# TopSheet.net
KiCad netlist of a schematic drawn in Altium Designer
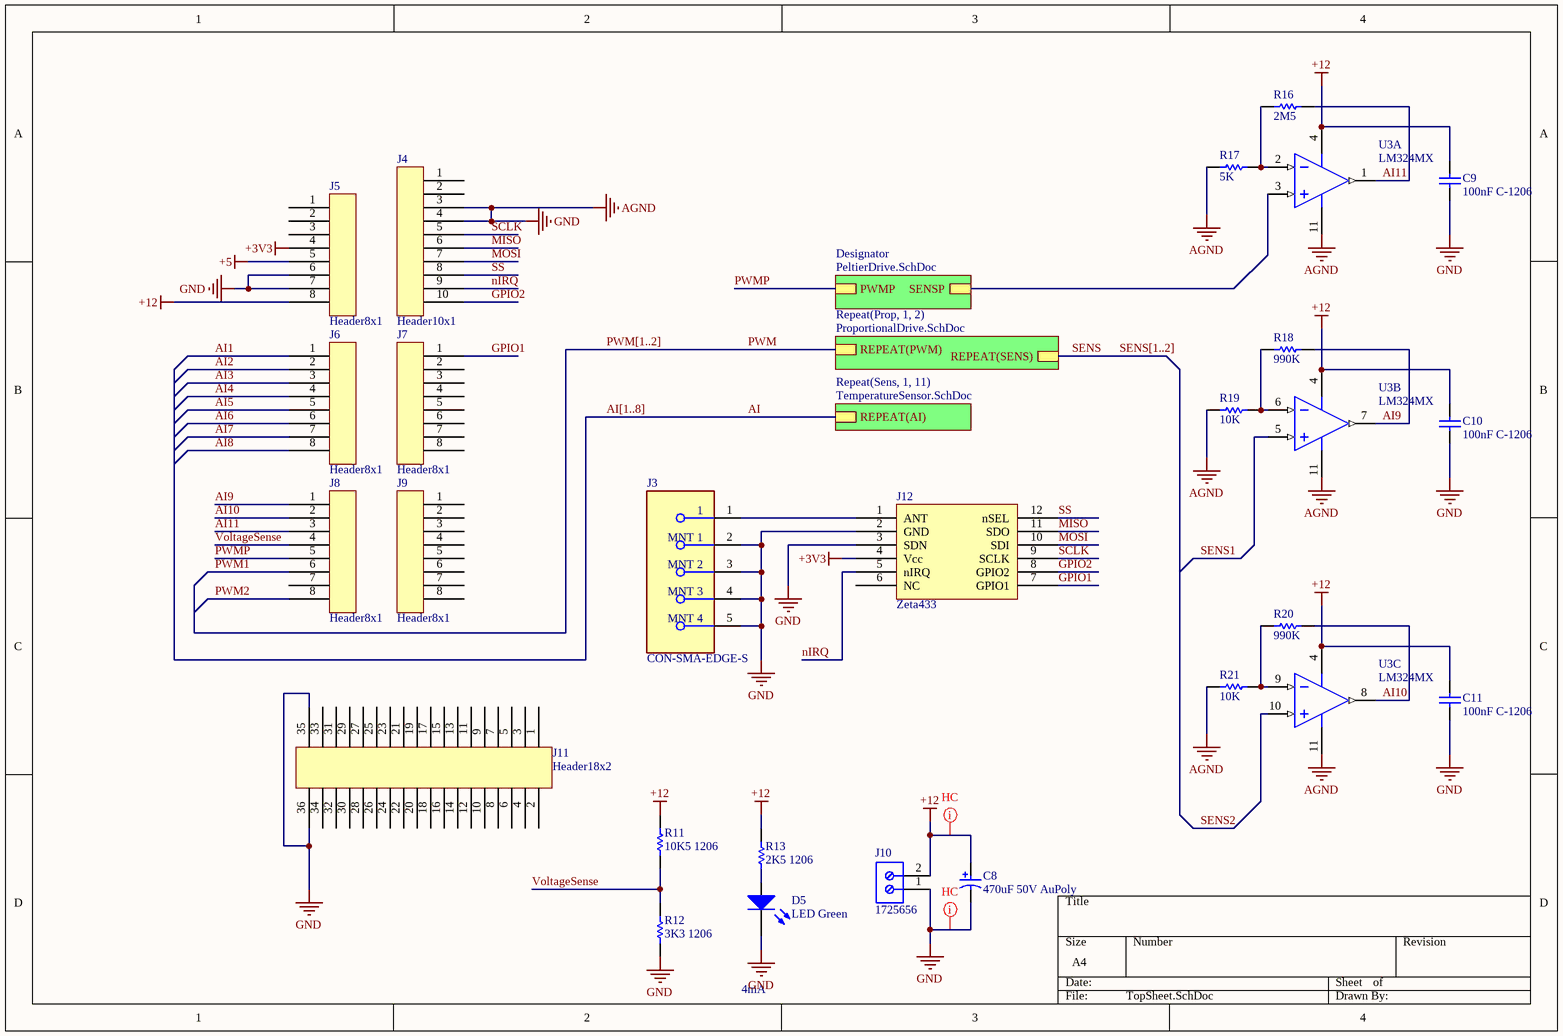
[diagram p0: TopSheet.SchDoc]

(export (version "E")
  (design (tool "Eeschema 10.0.6"))
  (components
    (comp (ref "C8")
      (value "470uF 50V AuPoly")
      (footprint "CAPAE137130X163M")
      (fields (field (name "VOLTAGE") "25VDC") (field (name "MANUFACTURER") "AVX"))
      (libsource (lib "Schlib1") (part "C-Poly"))
    )
    (comp (ref "C9")
      (value "100nF C-1206")
      (footprint "C-1206")
      (description "Ceramic 50V 1206")
      (fields (field (name "TOLERANCE") "Â±20%"))
      (libsource (lib "Schlib1") (part "C-1206"))
    )
    (comp (ref "C10")
      (value "100nF C-1206")
      (footprint "C-1206")
      (description "Ceramic 50V 1206")
      (fields (field (name "TOLERANCE") "Â±20%"))
      (libsource (lib "Schlib1") (part "C-1206"))
    )
    (comp (ref "C11")
      (value "100nF C-1206")
      (footprint "C-1206")
      (description "Ceramic 50V 1206")
      (fields (field (name "TOLERANCE") "Â±20%"))
      (libsource (lib "Schlib1") (part "C-1206"))
    )
    (comp (ref "D5")
      (value "LED Green")
      (footprint "0603_A")
      (description "SMD mono-color Chip LED, WL-SMCW, Green")
      (fields (field (name "PARTNUMBER") "150060GS75000") (field (name "MANUFACTURER") "Wuerth Elektronik"))
      (libsource (lib "Altium Content Vault") (part "WE-LED_K1A2-2"))
    )
    (comp (ref "J3")
      (value "CON-SMA-EDGE-S")
      (footprint "FP-CON-SMA-EDGE-S-MFG")
      (description "CONN SMA JACK STR EDGE MNT")
      (fields
        (field (name "OCTOPART") "https://octopart.com/con-sma-edge-s-rf+solutions-70967450")
        (field (name "MANUFACTURER") "RF Solutions Ltd.")
      )
      (libsource (lib "Altium Content Vault") (part "a163d97a771fcdd2fd1f1a9264c171f"))
    )
    (comp (ref "J4")
      (value "Header10x1")
      (footprint "Header10x1")
      (libsource (lib "Schlib1") (part "Header10x1"))
    )
    (comp (ref "J5")
      (value "Header8x1")
      (footprint "Header8x1")
      (libsource (lib "Schlib1") (part "Header8x1"))
    )
    (comp (ref "J6")
      (value "Header8x1")
      (footprint "Header8x1")
      (libsource (lib "Schlib1") (part "Header8x1"))
    )
    (comp (ref "J7") (value "Header8x1") (footprint "Header8x1") (libsource (lib "") (part "Header8x1_1")))
    (comp (ref "J8")
      (value "Header8x1")
      (footprint "Header8x1")
      (libsource (lib "Schlib1") (part "Header8x1"))
    )
    (comp (ref "J9") (value "Header8x1") (footprint "Header8x1") (libsource (lib "") (part "Header8x1_1")))
    (comp (ref "J10")
      (value "1725656")
      (footprint "PHOE-1725656-2")
      (description "Male Header, Pitch 2.54 mm, 1 x 2 Position, Height 9 mm, Tail Length 3.5 mm")
      (fields (field (name "MANUFACTURER") "Phoenix Contact"))
      (libsource (lib "Altium Content Vault") (part "CN-1P-F-TB2"))
    )
    (comp (ref "J11")
      (value "Header18x2")
      (footprint "Header18x2")
      (libsource (lib "Schlib1") (part "Header18x2"))
    )
    (comp (ref "J12") (value "Zeta433") (footprint "Zeta433-SM") (libsource (lib "Schlib1") (part "Zeta433")))
    (comp (ref "R11")
      (value "10K5 1206")
      (footprint "R-1206")
      (description "0.25W 1206")
      (fields (field (name "POWER") "0.1 W") (field (name "TOLERANCE") "1 %"))
      (libsource (lib "Schlib1") (part "R-1206"))
    )
    (comp (ref "R12")
      (value "3K3 1206")
      (footprint "R-1206")
      (description "0.25W 1206")
      (fields (field (name "POWER") "0.1 W") (field (name "TOLERANCE") "1 %"))
      (libsource (lib "Schlib1") (part "R-1206"))
    )
    (comp (ref "R13")
      (value "2K5 1206")
      (footprint "R-1206")
      (description "0.25W 1206")
      (fields (field (name "POWER") "0.1 W") (field (name "TOLERANCE") "1 %"))
      (libsource (lib "Schlib1") (part "R-1206"))
    )
    (comp (ref "R16")
      (value "2M5")
      (footprint "RESC0603(1608)_N")
      (description "10K 0.1W 1% 0603 (1608 Metric)  SMD")
      (fields (field (name "POWER") "0.1 W") (field (name "TOLERANCE") "1 %"))
      (libsource (lib "Altium Content Vault") (part "RES"))
    )
    (comp (ref "R17")
      (value "5K")
      (footprint "RESC0603(1608)_N")
      (description "10K 0.1W 1% 0603 (1608 Metric)  SMD")
      (fields (field (name "POWER") "0.1 W") (field (name "TOLERANCE") "1 %"))
      (libsource (lib "Altium Content Vault") (part "RES"))
    )
    (comp (ref "R18")
      (value "990K")
      (footprint "RESC0603(1608)_N")
      (description "10K 0.1W 1% 0603 (1608 Metric)  SMD")
      (fields (field (name "POWER") "0.1 W") (field (name "TOLERANCE") "1 %"))
      (libsource (lib "Altium Content Vault") (part "RES"))
    )
    (comp (ref "R19")
      (value "10K")
      (footprint "RESC0603(1608)_N")
      (description "10K 0.1W 1% 0603 (1608 Metric)  SMD")
      (fields (field (name "POWER") "0.1 W") (field (name "TOLERANCE") "1 %"))
      (libsource (lib "Altium Content Vault") (part "RES"))
    )
    (comp (ref "R20")
      (value "990K")
      (footprint "RESC0603(1608)_N")
      (description "10K 0.1W 1% 0603 (1608 Metric)  SMD")
      (fields (field (name "POWER") "0.1 W") (field (name "TOLERANCE") "1 %"))
      (libsource (lib "Altium Content Vault") (part "RES"))
    )
    (comp (ref "R21")
      (value "10K")
      (footprint "RESC0603(1608)_N")
      (description "10K 0.1W 1% 0603 (1608 Metric)  SMD")
      (fields (field (name "POWER") "0.1 W") (field (name "TOLERANCE") "1 %"))
      (libsource (lib "Altium Content Vault") (part "RES"))
    )
    (comp (ref "U3")
      (value "LM324MX")
      (footprint "D0014A_L")
      (description "Low Power Quad Operational Amplifier, 14-pin Narrow SOIC")
      (fields (field (name "MANUFACTURER") "Texas Instruments"))
      (libsource (lib "Altium Content Vault") (part "AMP-OPA-LM124-14"))
    )
  )
  (nets
    (net (code "1") (name "+3V3") (class "Default")
      (node (ref "J12") (pin "4") (pinfunction "Vcc_4") (pintype "passive"))
      (node (ref "J5") (pin "4") (pintype "passive"))
    )
    (net (code "2") (name "+5") (class "Default") (node (ref "J5") (pin "5") (pintype "passive")))
    (net (code "3") (name "+12") (class "Default")
      (node (ref "C10") (pin "2") (pinfunction "2_2") (pintype "passive"))
      (node (ref "C11") (pin "2") (pinfunction "2_2") (pintype "passive"))
      (node (ref "C8") (pin "1") (pinfunction "1_1") (pintype "passive"))
      (node (ref "C9") (pin "2") (pinfunction "2_2") (pintype "passive"))
      (node (ref "J10") (pin "2") (pinfunction "2_2") (pintype "passive"))
      (node (ref "J5") (pin "8") (pintype "passive"))
      (node (ref "R11") (pin "2") (pinfunction "2_2") (pintype "passive"))
      (node (ref "R13") (pin "2") (pinfunction "2_2") (pintype "passive"))
      (node (ref "U3") (pin "4") (pinfunction "V+_4") (pintype "power_in"))
    )
    (net (code "5") (name "/AI1") (class "Default") (node (ref "J6") (pin "1") (pintype "passive")))
    (net (code "6") (name "/AI2") (class "Default") (node (ref "J6") (pin "2") (pintype "passive")))
    (net (code "7") (name "/AI3") (class "Default") (node (ref "J6") (pin "3") (pintype "passive")))
    (net (code "8") (name "/AI4") (class "Default") (node (ref "J6") (pin "4") (pintype "passive")))
    (net (code "9") (name "/AI5") (class "Default") (node (ref "J6") (pin "5") (pintype "passive")))
    (net (code "10") (name "/AI6") (class "Default") (node (ref "J6") (pin "6") (pintype "passive")))
    (net (code "11") (name "/AI7") (class "Default") (node (ref "J6") (pin "7") (pintype "passive")))
    (net (code "12") (name "/AI8") (class "Default") (node (ref "J6") (pin "8") (pintype "passive")))
    (net (code "13") (name "/AI9") (class "Default")
      (node (ref "J8") (pin "1") (pintype "passive"))
      (node (ref "R18") (pin "2") (pinfunction "2_2") (pintype "passive"))
      (node (ref "U3") (pin "7") (pinfunction "OUT2_7") (pintype "output"))
    )
    (net (code "14") (name "/AI10") (class "Default")
      (node (ref "J8") (pin "2") (pintype "passive"))
      (node (ref "R20") (pin "2") (pinfunction "2_2") (pintype "passive"))
      (node (ref "U3") (pin "8") (pinfunction "OUT3_8") (pintype "output"))
    )
    (net (code "15") (name "/AI11") (class "Default")
      (node (ref "J8") (pin "3") (pintype "passive"))
      (node (ref "R16") (pin "2") (pinfunction "2_2") (pintype "passive"))
      (node (ref "U3") (pin "1") (pinfunction "OUT1_1") (pintype "output"))
    )
    (net (code "17") (name "/GPIO1") (class "Default")
      (node (ref "J12") (pin "7") (pinfunction "GPIO1_7") (pintype "passive"))
      (node (ref "J7") (pin "1") (pintype "passive"))
    )
    (net (code "18") (name "/GPIO2") (class "Default")
      (node (ref "J12") (pin "8") (pinfunction "GPIO2_8") (pintype "passive"))
      (node (ref "J4") (pin "10") (pintype "passive"))
    )
    (net (code "19") (name "/MISO") (class "Default")
      (node (ref "J12") (pin "11") (pinfunction "SDO_11") (pintype "passive"))
      (node (ref "J4") (pin "6") (pintype "passive"))
    )
    (net (code "20") (name "/MOSI") (class "Default")
      (node (ref "J12") (pin "10") (pinfunction "SDI_10") (pintype "passive"))
      (node (ref "J4") (pin "7") (pintype "passive"))
    )
    (net (code "22") (name "/PWM1") (class "Default") (node (ref "J8") (pin "6") (pintype "passive")))
    (net (code "23") (name "/PWM2") (class "Default") (node (ref "J8") (pin "8") (pintype "passive")))
    (net (code "24") (name "/PWMP") (class "Default") (node (ref "J8") (pin "5") (pintype "passive")))
    (net (code "26") (name "/SCLK") (class "Default")
      (node (ref "J12") (pin "9") (pinfunction "SCLK_9") (pintype "passive"))
      (node (ref "J4") (pin "5") (pintype "passive"))
    )
    (net (code "28") (name "/SENS1") (class "Default")
      (node (ref "U3") (pin "5") (pinfunction "IN2+_5") (pintype "input"))
    )
    (net (code "29") (name "/SENS2") (class "Default")
      (node (ref "U3") (pin "10") (pinfunction "IN3+_10") (pintype "input"))
    )
    (net (code "30") (name "/SENSP") (class "Default")
      (node (ref "U3") (pin "3") (pinfunction "IN1+_3") (pintype "input"))
    )
    (net (code "32") (name "/SS") (class "Default")
      (node (ref "J12") (pin "12") (pinfunction "nSEL_12") (pintype "passive"))
      (node (ref "J4") (pin "8") (pintype "passive"))
    )
    (net (code "33") (name "/VoltageSense") (class "Default")
      (node (ref "J8") (pin "4") (pintype "passive"))
      (node (ref "R11") (pin "1") (pinfunction "1_1") (pintype "passive"))
      (node (ref "R12") (pin "2") (pinfunction "2_2") (pintype "passive"))
    )
    (net (code "34") (name "/nIRQ") (class "Default")
      (node (ref "J12") (pin "5") (pinfunction "nIRQ_5") (pintype "passive"))
      (node (ref "J4") (pin "9") (pintype "passive"))
    )
    (net (code "35") (name "AGND") (class "Default")
      (node (ref "C10") (pin "1") (pinfunction "1_1") (pintype "passive"))
      (node (ref "C11") (pin "1") (pinfunction "1_1") (pintype "passive"))
      (node (ref "C8") (pin "2") (pinfunction "2_2") (pintype "passive"))
      (node (ref "C9") (pin "1") (pinfunction "1_1") (pintype "passive"))
      (node (ref "D5") (pin "1") (pinfunction "K_1") (pintype "passive"))
      (node (ref "J10") (pin "1") (pinfunction "1_1") (pintype "passive"))
      (node (ref "J11") (pin "35") (pintype "passive"))
      (node (ref "J11") (pin "36") (pintype "passive"))
      (node (ref "J12") (pin "2") (pinfunction "GND_2") (pintype "passive"))
      (node (ref "J12") (pin "3") (pinfunction "SDN_3") (pintype "passive"))
      (node (ref "J3") (pin "2") (pinfunction "MNT_1_2") (pintype "passive"))
      (node (ref "J3") (pin "3") (pinfunction "MNT_2_3") (pintype "passive"))
      (node (ref "J3") (pin "4") (pinfunction "MNT_3_4") (pintype "passive"))
      (node (ref "J3") (pin "5") (pinfunction "MNT_4_5") (pintype "passive"))
      (node (ref "J4") (pin "3") (pintype "passive"))
      (node (ref "J4") (pin "4") (pintype "passive"))
      (node (ref "J5") (pin "6") (pintype "passive"))
      (node (ref "J5") (pin "7") (pintype "passive"))
      (node (ref "R12") (pin "1") (pinfunction "1_1") (pintype "passive"))
      (node (ref "R17") (pin "1") (pinfunction "1_1") (pintype "passive"))
      (node (ref "R19") (pin "1") (pinfunction "1_1") (pintype "passive"))
      (node (ref "R21") (pin "1") (pinfunction "1_1") (pintype "passive"))
      (node (ref "U3") (pin "11") (pinfunction "GND_11") (pintype "power_in"))
    )
    (net (code "36") (name "Net-(D5-A)") (class "Default")
      (node (ref "D5") (pin "2") (pinfunction "A_2") (pintype "passive"))
      (node (ref "R13") (pin "1") (pinfunction "1_1") (pintype "passive"))
    )
    (net (code "37") (name "Net-(J12-ANT)") (class "Default")
      (node (ref "J12") (pin "1") (pinfunction "ANT_1") (pintype "passive"))
      (node (ref "J3") (pin "1") (pinfunction "1_1") (pintype "passive"))
    )
    (net (code "38") (name "Net-(U3A-IN1-)") (class "Default")
      (node (ref "R16") (pin "1") (pinfunction "1_1") (pintype "passive"))
      (node (ref "R17") (pin "2") (pinfunction "2_2") (pintype "passive"))
      (node (ref "U3") (pin "2") (pinfunction "IN1-_2") (pintype "input"))
    )
    (net (code "39") (name "Net-(U3B-IN2-)") (class "Default")
      (node (ref "R18") (pin "1") (pinfunction "1_1") (pintype "passive"))
      (node (ref "R19") (pin "2") (pinfunction "2_2") (pintype "passive"))
      (node (ref "U3") (pin "6") (pinfunction "IN2-_6") (pintype "input"))
    )
    (net (code "40") (name "Net-(U3C-IN3-)") (class "Default")
      (node (ref "R20") (pin "1") (pinfunction "1_1") (pintype "passive"))
      (node (ref "R21") (pin "2") (pinfunction "2_2") (pintype "passive"))
      (node (ref "U3") (pin "9") (pinfunction "IN3-_9") (pintype "input"))
    )
    (net (code "41") (name "unconnected-(J4-Pad1)") (class "Default")
      (node (ref "J4") (pin "1") (pintype "passive"))
    )
    (net (code "42") (name "unconnected-(J4-Pad2)") (class "Default")
      (node (ref "J4") (pin "2") (pintype "passive"))
    )
    (net (code "43") (name "unconnected-(J5-Pad1)") (class "Default")
      (node (ref "J5") (pin "1") (pintype "passive"))
    )
    (net (code "44") (name "unconnected-(J5-Pad2)") (class "Default")
      (node (ref "J5") (pin "2") (pintype "passive"))
    )
    (net (code "45") (name "unconnected-(J5-Pad3)") (class "Default")
      (node (ref "J5") (pin "3") (pintype "passive"))
    )
    (net (code "46") (name "unconnected-(J7-Pad2)") (class "Default")
      (node (ref "J7") (pin "2") (pintype "passive"))
    )
    (net (code "47") (name "unconnected-(J7-Pad3)") (class "Default")
      (node (ref "J7") (pin "3") (pintype "passive"))
    )
    (net (code "48") (name "unconnected-(J7-Pad4)") (class "Default")
      (node (ref "J7") (pin "4") (pintype "passive"))
    )
    (net (code "49") (name "unconnected-(J7-Pad5)") (class "Default")
      (node (ref "J7") (pin "5") (pintype "passive"))
    )
    (net (code "50") (name "unconnected-(J7-Pad6)") (class "Default")
      (node (ref "J7") (pin "6") (pintype "passive"))
    )
    (net (code "51") (name "unconnected-(J7-Pad7)") (class "Default")
      (node (ref "J7") (pin "7") (pintype "passive"))
    )
    (net (code "52") (name "unconnected-(J7-Pad8)") (class "Default")
      (node (ref "J7") (pin "8") (pintype "passive"))
    )
    (net (code "53") (name "unconnected-(J8-Pad7)") (class "Default")
      (node (ref "J8") (pin "7") (pintype "passive"))
    )
    (net (code "54") (name "unconnected-(J9-Pad1)") (class "Default")
      (node (ref "J9") (pin "1") (pintype "passive"))
    )
    (net (code "55") (name "unconnected-(J9-Pad2)") (class "Default")
      (node (ref "J9") (pin "2") (pintype "passive"))
    )
    (net (code "56") (name "unconnected-(J9-Pad3)") (class "Default")
      (node (ref "J9") (pin "3") (pintype "passive"))
    )
    (net (code "57") (name "unconnected-(J9-Pad4)") (class "Default")
      (node (ref "J9") (pin "4") (pintype "passive"))
    )
    (net (code "58") (name "unconnected-(J9-Pad5)") (class "Default")
      (node (ref "J9") (pin "5") (pintype "passive"))
    )
    (net (code "59") (name "unconnected-(J9-Pad6)") (class "Default")
      (node (ref "J9") (pin "6") (pintype "passive"))
    )
    (net (code "60") (name "unconnected-(J9-Pad7)") (class "Default")
      (node (ref "J9") (pin "7") (pintype "passive"))
    )
    (net (code "61") (name "unconnected-(J9-Pad8)") (class "Default")
      (node (ref "J9") (pin "8") (pintype "passive"))
    )
    (net (code "62") (name "unconnected-(J11-Pad1)") (class "Default")
      (node (ref "J11") (pin "1") (pintype "passive"))
    )
    (net (code "63") (name "unconnected-(J11-Pad2)") (class "Default")
      (node (ref "J11") (pin "2") (pintype "passive"))
    )
    (net (code "64") (name "unconnected-(J11-Pad3)") (class "Default")
      (node (ref "J11") (pin "3") (pintype "passive"))
    )
    (net (code "65") (name "unconnected-(J11-Pad4)") (class "Default")
      (node (ref "J11") (pin "4") (pintype "passive"))
    )
    (net (code "66") (name "unconnected-(J11-Pad5)") (class "Default")
      (node (ref "J11") (pin "5") (pintype "passive"))
    )
    (net (code "67") (name "unconnected-(J11-Pad6)") (class "Default")
      (node (ref "J11") (pin "6") (pintype "passive"))
    )
    (net (code "68") (name "unconnected-(J11-Pad7)") (class "Default")
      (node (ref "J11") (pin "7") (pintype "passive"))
    )
    (net (code "69") (name "unconnected-(J11-Pad8)") (class "Default")
      (node (ref "J11") (pin "8") (pintype "passive"))
    )
    (net (code "70") (name "unconnected-(J11-Pad9)") (class "Default")
      (node (ref "J11") (pin "9") (pintype "passive"))
    )
    (net (code "71") (name "unconnected-(J11-Pad10)") (class "Default")
      (node (ref "J11") (pin "10") (pintype "passive"))
    )
    (net (code "72") (name "unconnected-(J11-Pad11)") (class "Default")
      (node (ref "J11") (pin "11") (pintype "passive"))
    )
    (net (code "73") (name "unconnected-(J11-Pad12)") (class "Default")
      (node (ref "J11") (pin "12") (pintype "passive"))
    )
    (net (code "74") (name "unconnected-(J11-Pad13)") (class "Default")
      (node (ref "J11") (pin "13") (pintype "passive"))
    )
    (net (code "75") (name "unconnected-(J11-Pad14)") (class "Default")
      (node (ref "J11") (pin "14") (pintype "passive"))
    )
    (net (code "76") (name "unconnected-(J11-Pad15)") (class "Default")
      (node (ref "J11") (pin "15") (pintype "passive"))
    )
    (net (code "77") (name "unconnected-(J11-Pad16)") (class "Default")
      (node (ref "J11") (pin "16") (pintype "passive"))
    )
    (net (code "78") (name "unconnected-(J11-Pad17)") (class "Default")
      (node (ref "J11") (pin "17") (pintype "passive"))
    )
    (net (code "79") (name "unconnected-(J11-Pad18)") (class "Default")
      (node (ref "J11") (pin "18") (pintype "passive"))
    )
    (net (code "80") (name "unconnected-(J11-Pad19)") (class "Default")
      (node (ref "J11") (pin "19") (pintype "passive"))
    )
    (net (code "81") (name "unconnected-(J11-Pad20)") (class "Default")
      (node (ref "J11") (pin "20") (pintype "passive"))
    )
    (net (code "82") (name "unconnected-(J11-Pad21)") (class "Default")
      (node (ref "J11") (pin "21") (pintype "passive"))
    )
    (net (code "83") (name "unconnected-(J11-Pad22)") (class "Default")
      (node (ref "J11") (pin "22") (pintype "passive"))
    )
    (net (code "84") (name "unconnected-(J11-Pad23)") (class "Default")
      (node (ref "J11") (pin "23") (pintype "passive"))
    )
    (net (code "85") (name "unconnected-(J11-Pad24)") (class "Default")
      (node (ref "J11") (pin "24") (pintype "passive"))
    )
    (net (code "86") (name "unconnected-(J11-Pad25)") (class "Default")
      (node (ref "J11") (pin "25") (pintype "passive"))
    )
    (net (code "87") (name "unconnected-(J11-Pad26)") (class "Default")
      (node (ref "J11") (pin "26") (pintype "passive"))
    )
    (net (code "88") (name "unconnected-(J11-Pad27)") (class "Default")
      (node (ref "J11") (pin "27") (pintype "passive"))
    )
    (net (code "89") (name "unconnected-(J11-Pad28)") (class "Default")
      (node (ref "J11") (pin "28") (pintype "passive"))
    )
    (net (code "90") (name "unconnected-(J11-Pad29)") (class "Default")
      (node (ref "J11") (pin "29") (pintype "passive"))
    )
    (net (code "91") (name "unconnected-(J11-Pad30)") (class "Default")
      (node (ref "J11") (pin "30") (pintype "passive"))
    )
    (net (code "92") (name "unconnected-(J11-Pad31)") (class "Default")
      (node (ref "J11") (pin "31") (pintype "passive"))
    )
    (net (code "93") (name "unconnected-(J11-Pad32)") (class "Default")
      (node (ref "J11") (pin "32") (pintype "passive"))
    )
    (net (code "94") (name "unconnected-(J11-Pad33)") (class "Default")
      (node (ref "J11") (pin "33") (pintype "passive"))
    )
    (net (code "95") (name "unconnected-(J11-Pad34)") (class "Default")
      (node (ref "J11") (pin "34") (pintype "passive"))
    )
    (net (code "96") (name "unconnected-(J12-NC-Pad6)") (class "Default")
      (node (ref "J12") (pin "6") (pinfunction "NC_6") (pintype "passive"))
    )
  )
)
